# TEC_CTRL.net
KiCad netlist of a schematic drawn in Altium Designer
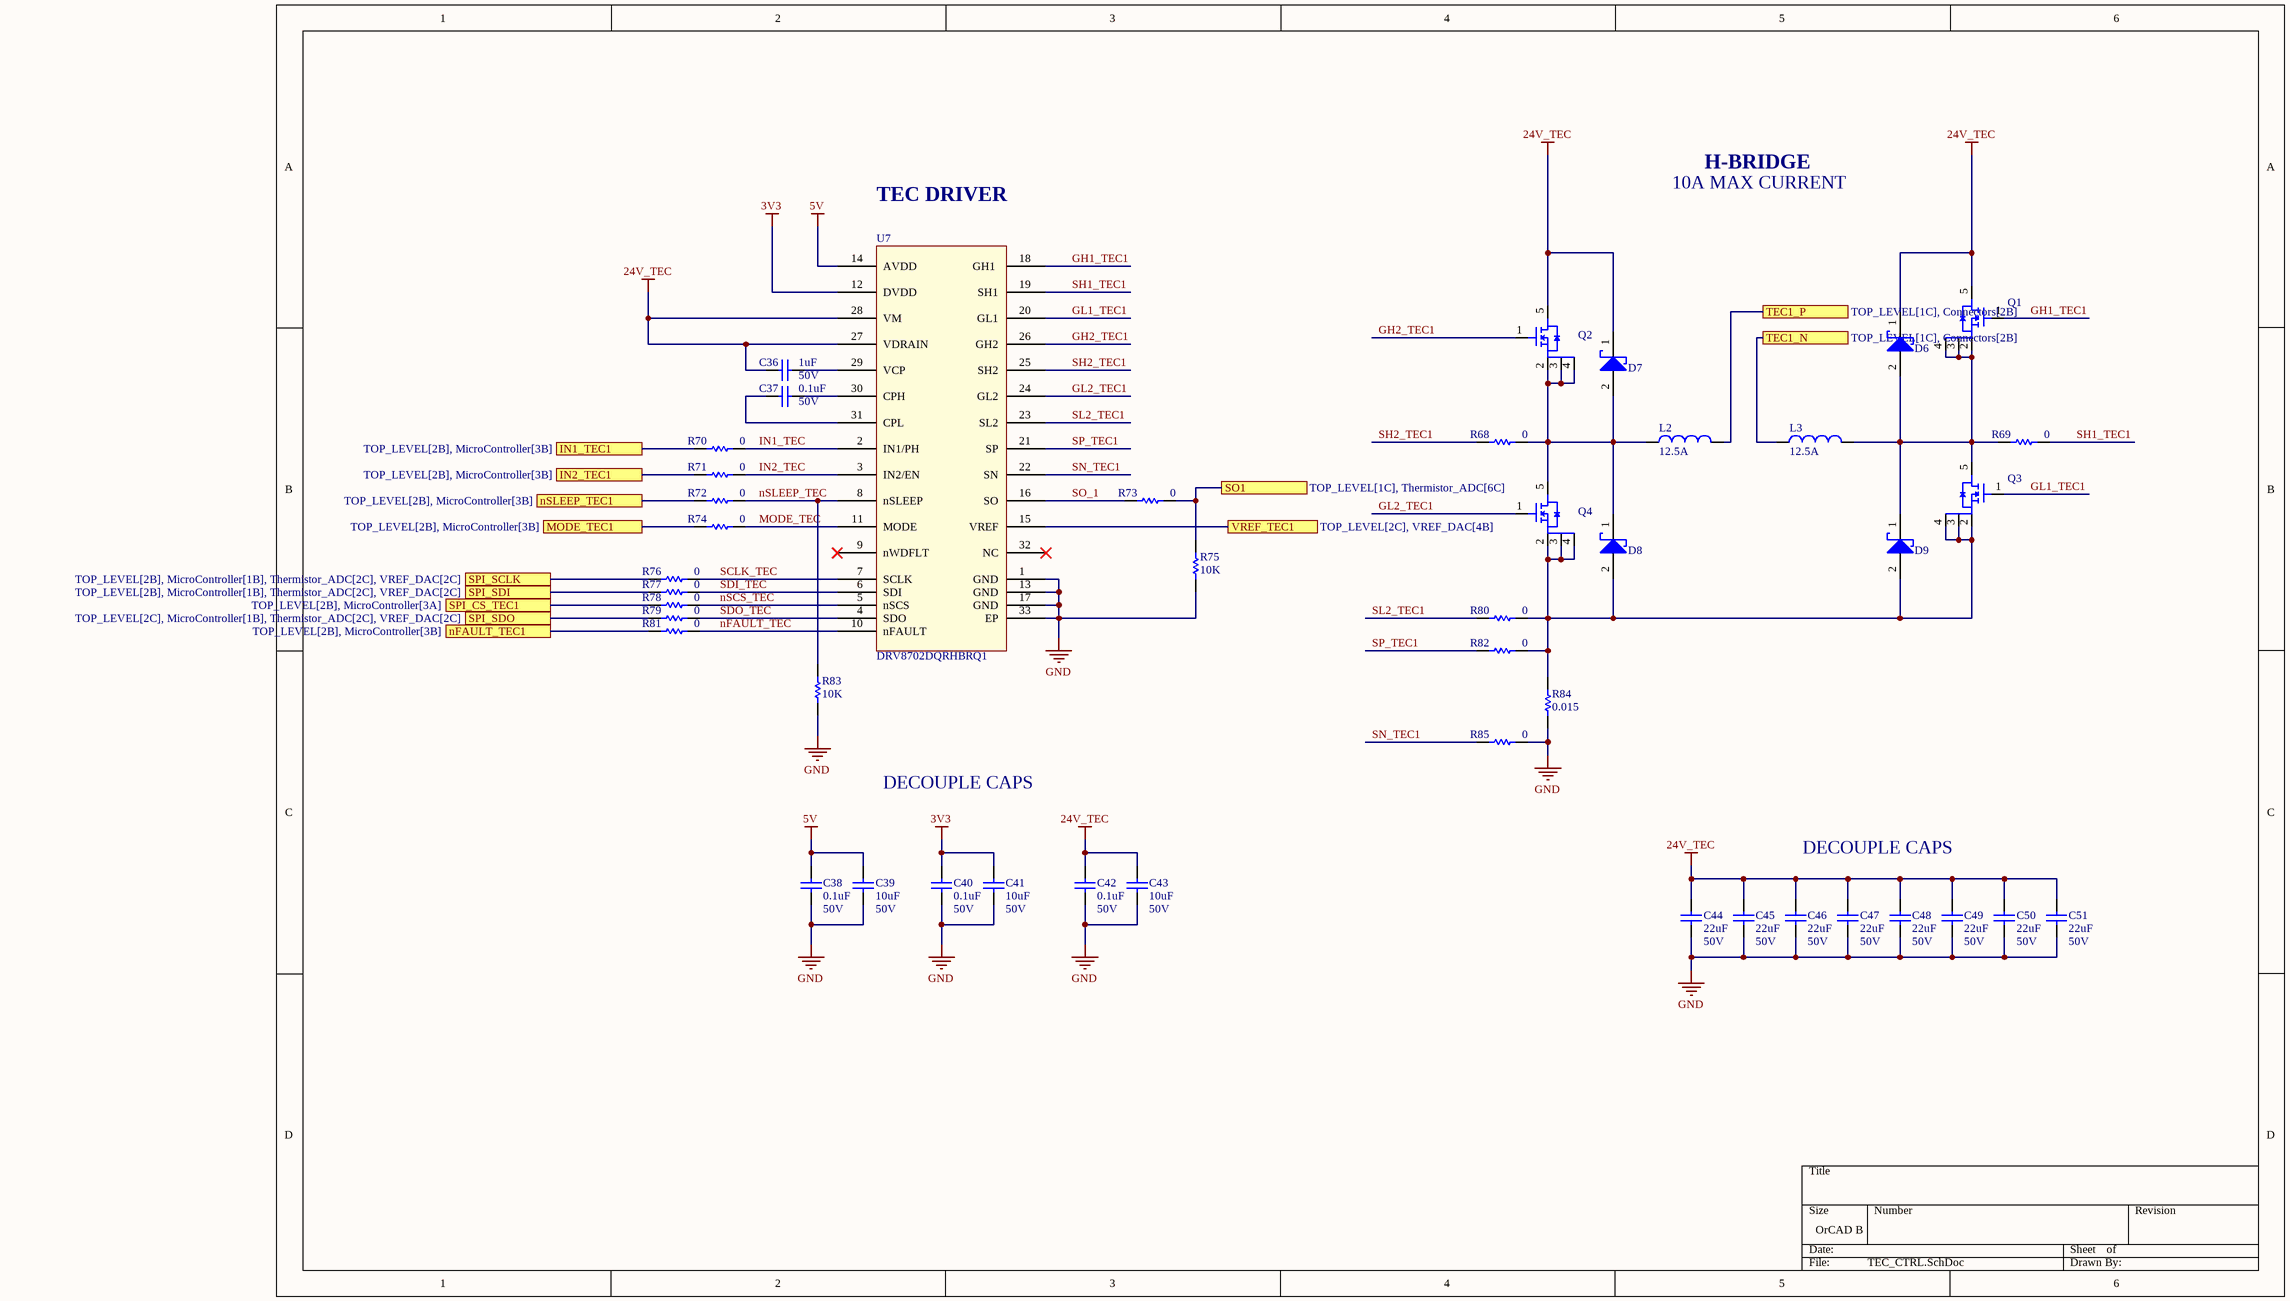
[diagram p0: TEC_CTRL.SchDoc]

(export (version "E")
  (design (tool "Eeschema 10.0.6"))
  (components
    (comp (ref "C36")
      (value "1uF")
      (footprint "DEFAULT_CAPACITOR_0805")
      (description "CAP CER 1UF 50V X7R 0805")
      (fields (field (name "RATING") "50V") (field (name "Comment") "CL21B105KBFNNNE"))
      (libsource (lib "Avery Altium Llibrary") (part "CL21B105KBFNNNE"))
    )
    (comp (ref "C37")
      (value "0.1uF")
      (footprint "DEFAULT_CAPACITOR_0805")
      (description "CAP CER 0.1UF 50V X7R 0805")
      (fields
        (field (name "MANUFACTURER") "Cal-Chip Electronics, Inc.")
        (field (name "RATING") "50V")
        (field (name "Comment") "KGM21NR71H104KT")
      )
      (libsource (lib "Avery Altium Llibrary") (part "KGM21NR71H104KT"))
    )
    (comp (ref "C38")
      (value "0.1uF")
      (footprint "DEFAULT_CAPACITOR_0805")
      (description "CAP CER 0.1UF 50V X7R 0805")
      (fields
        (field (name "MANUFACTURER") "Cal-Chip Electronics, Inc.")
        (field (name "RATING") "50V")
        (field (name "Comment") "KGM21NR71H104KT")
      )
      (libsource (lib "Avery Altium Llibrary") (part "KGM21NR71H104KT"))
    )
    (comp (ref "C39")
      (value "10uF")
      (footprint "DEFAULT_CAPACITOR_0805")
      (description "CAP CER 10UF 50V X5R 0805")
      (fields (field (name "RATING") "50V") (field (name "Comment") "GRM21BR61H106KE43L"))
      (libsource (lib "Avery Altium Llibrary") (part "GRM21BR61H106KE43L"))
    )
    (comp (ref "C40")
      (value "0.1uF")
      (footprint "DEFAULT_CAPACITOR_0805")
      (description "CAP CER 0.1UF 50V X7R 0805")
      (fields
        (field (name "MANUFACTURER") "Cal-Chip Electronics, Inc.")
        (field (name "RATING") "50V")
        (field (name "Comment") "KGM21NR71H104KT")
      )
      (libsource (lib "Avery Altium Llibrary") (part "KGM21NR71H104KT"))
    )
    (comp (ref "C41")
      (value "10uF")
      (footprint "DEFAULT_CAPACITOR_0805")
      (description "CAP CER 10UF 50V X5R 0805")
      (fields (field (name "RATING") "50V") (field (name "Comment") "GRM21BR61H106KE43L"))
      (libsource (lib "Avery Altium Llibrary") (part "GRM21BR61H106KE43L"))
    )
    (comp (ref "C42")
      (value "0.1uF")
      (footprint "DEFAULT_CAPACITOR_0805")
      (description "CAP CER 0.1UF 50V X7R 0805")
      (fields
        (field (name "MANUFACTURER") "Cal-Chip Electronics, Inc.")
        (field (name "RATING") "50V")
        (field (name "Comment") "KGM21NR71H104KT")
      )
      (libsource (lib "Avery Altium Llibrary") (part "KGM21NR71H104KT"))
    )
    (comp (ref "C43")
      (value "10uF")
      (footprint "DEFAULT_CAPACITOR_0805")
      (description "CAP CER 10UF 50V X5R 0805")
      (fields (field (name "RATING") "50V") (field (name "Comment") "GRM21BR61H106KE43L"))
      (libsource (lib "Avery Altium Llibrary") (part "GRM21BR61H106KE43L"))
    )
    (comp (ref "C44")
      (value "22uF")
      (footprint "DEFAULT_CAPACITOR_2220")
      (description "CAP CER 22UF 50V X7R 2220")
      (fields (field (name "RATING") "50V") (field (name "Comment") "C5750X7R1H226M250KB"))
      (libsource (lib "Avery Altium Llibrary") (part "C5750X7R1H226M250KB"))
    )
    (comp (ref "C45")
      (value "22uF")
      (footprint "DEFAULT_CAPACITOR_2220")
      (description "CAP CER 22UF 50V X7R 2220")
      (fields (field (name "RATING") "50V") (field (name "Comment") "C5750X7R1H226M250KB"))
      (libsource (lib "Avery Altium Llibrary") (part "C5750X7R1H226M250KB"))
    )
    (comp (ref "C46")
      (value "22uF")
      (footprint "DEFAULT_CAPACITOR_2220")
      (description "CAP CER 22UF 50V X7R 2220")
      (fields (field (name "RATING") "50V") (field (name "Comment") "C5750X7R1H226M250KB"))
      (libsource (lib "Avery Altium Llibrary") (part "C5750X7R1H226M250KB"))
    )
    (comp (ref "C47")
      (value "22uF")
      (footprint "DEFAULT_CAPACITOR_2220")
      (description "CAP CER 22UF 50V X7R 2220")
      (fields (field (name "RATING") "50V") (field (name "Comment") "C5750X7R1H226M250KB"))
      (libsource (lib "Avery Altium Llibrary") (part "C5750X7R1H226M250KB"))
    )
    (comp (ref "C48")
      (value "22uF")
      (footprint "DEFAULT_CAPACITOR_2220")
      (description "CAP CER 22UF 50V X7R 2220")
      (fields (field (name "RATING") "50V") (field (name "Comment") "C5750X7R1H226M250KB"))
      (libsource (lib "Avery Altium Llibrary") (part "C5750X7R1H226M250KB"))
    )
    (comp (ref "C49")
      (value "22uF")
      (footprint "DEFAULT_CAPACITOR_2220")
      (description "CAP CER 22UF 50V X7R 2220")
      (fields (field (name "RATING") "50V") (field (name "Comment") "C5750X7R1H226M250KB"))
      (libsource (lib "Avery Altium Llibrary") (part "C5750X7R1H226M250KB"))
    )
    (comp (ref "C50")
      (value "22uF")
      (footprint "DEFAULT_CAPACITOR_2220")
      (description "CAP CER 22UF 50V X7R 2220")
      (fields (field (name "RATING") "50V") (field (name "Comment") "C5750X7R1H226M250KB"))
      (libsource (lib "Avery Altium Llibrary") (part "C5750X7R1H226M250KB"))
    )
    (comp (ref "C51")
      (value "22uF")
      (footprint "DEFAULT_CAPACITOR_2220")
      (description "CAP CER 22UF 50V X7R 2220")
      (fields (field (name "RATING") "50V") (field (name "Comment") "C5750X7R1H226M250KB"))
      (libsource (lib "Avery Altium Llibrary") (part "C5750X7R1H226M250KB"))
    )
    (comp (ref "D6")
      (value "B2100Q-13-F")
      (footprint "B2100Q-13-F-SMB")
      (description "DIODE SCHOTTKY 100V 2A SMB")
      (fields (field (name "MANUFACTURER") "Diodes Incorporated"))
      (libsource (lib "Avery Altium Llibrary") (part "B2100Q-13-F"))
    )
    (comp (ref "D7")
      (value "B2100Q-13-F")
      (footprint "B2100Q-13-F-SMB")
      (description "DIODE SCHOTTKY 100V 2A SMB")
      (fields (field (name "MANUFACTURER") "Diodes Incorporated"))
      (libsource (lib "Avery Altium Llibrary") (part "B2100Q-13-F"))
    )
    (comp (ref "D8")
      (value "B2100Q-13-F")
      (footprint "B2100Q-13-F-SMB")
      (description "DIODE SCHOTTKY 100V 2A SMB")
      (fields (field (name "MANUFACTURER") "Diodes Incorporated"))
      (libsource (lib "Avery Altium Llibrary") (part "B2100Q-13-F"))
    )
    (comp (ref "D9")
      (value "B2100Q-13-F")
      (footprint "B2100Q-13-F-SMB")
      (description "DIODE SCHOTTKY 100V 2A SMB")
      (fields (field (name "MANUFACTURER") "Diodes Incorporated"))
      (libsource (lib "Avery Altium Llibrary") (part "B2100Q-13-F"))
    )
    (comp (ref "L2")
      (value "SRP1770TA-150M")
      (footprint "BOURNS-SRP1770TA")
      (description "FIXED IND 15UH 12.5A 20.5MOHM SM")
      (fields (field (name "MANUFACTURER") "Bourns Inc.") (field (name "RATING") "12.5A"))
      (libsource (lib "Avery Schem Library") (part "SRP1770TA-150M"))
    )
    (comp (ref "L3")
      (value "SRP1770TA-150M")
      (footprint "BOURNS-SRP1770TA")
      (description "FIXED IND 15UH 12.5A 20.5MOHM SM")
      (fields (field (name "MANUFACTURER") "Bourns Inc.") (field (name "RATING") "12.5A"))
      (libsource (lib "Avery Schem Library") (part "SRP1770TA-150M"))
    )
    (comp (ref "Q1")
      (value "BUK7S2R0-40HJ")
      (footprint "BUK7S2R0-40HJ-SOT1235")
      (description "N-Channel 40 V 190A (Tc) 183W (Tc) Surface Mount LFPAK88 (SOT1235)")
      (fields (field (name "MANUFACTURER") "Nexperia USA Inc."))
      (libsource (lib "Avery Altium Llibrary") (part "BUK7S2R0-40HJ"))
    )
    (comp (ref "Q2")
      (value "BUK7S2R0-40HJ")
      (footprint "BUK7S2R0-40HJ-SOT1235")
      (description "N-Channel 40 V 190A (Tc) 183W (Tc) Surface Mount LFPAK88 (SOT1235)")
      (fields (field (name "MANUFACTURER") "Nexperia USA Inc."))
      (libsource (lib "Avery Altium Llibrary") (part "BUK7S2R0-40HJ"))
    )
    (comp (ref "Q3")
      (value "BUK7S2R0-40HJ")
      (footprint "BUK7S2R0-40HJ-SOT1235")
      (description "N-Channel 40 V 190A (Tc) 183W (Tc) Surface Mount LFPAK88 (SOT1235)")
      (fields (field (name "MANUFACTURER") "Nexperia USA Inc."))
      (libsource (lib "Avery Altium Llibrary") (part "BUK7S2R0-40HJ"))
    )
    (comp (ref "Q4")
      (value "BUK7S2R0-40HJ")
      (footprint "BUK7S2R0-40HJ-SOT1235")
      (description "N-Channel 40 V 190A (Tc) 183W (Tc) Surface Mount LFPAK88 (SOT1235)")
      (fields (field (name "MANUFACTURER") "Nexperia USA Inc."))
      (libsource (lib "Avery Altium Llibrary") (part "BUK7S2R0-40HJ"))
    )
    (comp (ref "R68")
      (value "0")
      (footprint "DEFAULT_RESISTOR_0805")
      (description "RES 0 OHM JUMPER 1/8W 0805")
      (fields (field (name "POWER") "1/8W") (field (name "Comment") "RC0805JR-070RL"))
      (libsource (lib "Avery Altium Llibrary") (part "RC0805JR-070RL"))
    )
    (comp (ref "R69")
      (value "0")
      (footprint "DEFAULT_RESISTOR_0805")
      (description "RES 0 OHM JUMPER 1/8W 0805")
      (fields (field (name "POWER") "1/8W") (field (name "Comment") "RC0805JR-070RL"))
      (libsource (lib "Avery Altium Llibrary") (part "RC0805JR-070RL"))
    )
    (comp (ref "R70")
      (value "0")
      (footprint "DEFAULT_RESISTOR_0805")
      (description "RES 0 OHM JUMPER 1/8W 0805")
      (fields (field (name "POWER") "1/8W") (field (name "Comment") "RC0805JR-070RL"))
      (libsource (lib "Avery Altium Llibrary") (part "RC0805JR-070RL"))
    )
    (comp (ref "R71")
      (value "0")
      (footprint "DEFAULT_RESISTOR_0805")
      (description "RES 0 OHM JUMPER 1/8W 0805")
      (fields (field (name "POWER") "1/8W") (field (name "Comment") "RC0805JR-070RL"))
      (libsource (lib "Avery Altium Llibrary") (part "RC0805JR-070RL"))
    )
    (comp (ref "R72")
      (value "0")
      (footprint "DEFAULT_RESISTOR_0805")
      (description "RES 0 OHM JUMPER 1/8W 0805")
      (fields (field (name "POWER") "1/8W") (field (name "Comment") "RC0805JR-070RL"))
      (libsource (lib "Avery Altium Llibrary") (part "RC0805JR-070RL"))
    )
    (comp (ref "R73")
      (value "0")
      (footprint "DEFAULT_RESISTOR_0805")
      (description "RES 0 OHM JUMPER 1/8W 0805")
      (fields (field (name "POWER") "1/8W") (field (name "Comment") "RC0805JR-070RL"))
      (libsource (lib "Avery Altium Llibrary") (part "RC0805JR-070RL"))
    )
    (comp (ref "R74")
      (value "0")
      (footprint "DEFAULT_RESISTOR_0805")
      (description "RES 0 OHM JUMPER 1/8W 0805")
      (fields (field (name "POWER") "1/8W") (field (name "Comment") "RC0805JR-070RL"))
      (libsource (lib "Avery Altium Llibrary") (part "RC0805JR-070RL"))
    )
    (comp (ref "R75")
      (value "10K")
      (footprint "DEFAULT_RESISTOR_0805")
      (description "RES SMD 10K OHM 1% 1/4W 0805")
      (fields (field (name "POWER") "1/4W") (field (name "TOLERANCE") "1%"))
      (libsource (lib "Avery Altium Llibrary") (part "CRCW080510K0FKEA"))
    )
    (comp (ref "R76")
      (value "0")
      (footprint "DEFAULT_RESISTOR_0805")
      (description "RES 0 OHM JUMPER 1/8W 0805")
      (fields (field (name "POWER") "1/8W") (field (name "Comment") "RC0805JR-070RL"))
      (libsource (lib "Avery Altium Llibrary") (part "RC0805JR-070RL"))
    )
    (comp (ref "R77")
      (value "0")
      (footprint "DEFAULT_RESISTOR_0805")
      (description "RES 0 OHM JUMPER 1/8W 0805")
      (fields (field (name "POWER") "1/8W") (field (name "Comment") "RC0805JR-070RL"))
      (libsource (lib "Avery Altium Llibrary") (part "RC0805JR-070RL"))
    )
    (comp (ref "R78")
      (value "0")
      (footprint "DEFAULT_RESISTOR_0805")
      (description "RES 0 OHM JUMPER 1/8W 0805")
      (fields (field (name "POWER") "1/8W") (field (name "Comment") "RC0805JR-070RL"))
      (libsource (lib "Avery Altium Llibrary") (part "RC0805JR-070RL"))
    )
    (comp (ref "R79")
      (value "0")
      (footprint "DEFAULT_RESISTOR_0805")
      (description "RES 0 OHM JUMPER 1/8W 0805")
      (fields (field (name "POWER") "1/8W") (field (name "Comment") "RC0805JR-070RL"))
      (libsource (lib "Avery Altium Llibrary") (part "RC0805JR-070RL"))
    )
    (comp (ref "R80")
      (value "0")
      (footprint "DEFAULT_RESISTOR_0805")
      (description "RES 0 OHM JUMPER 1/8W 0805")
      (fields (field (name "POWER") "1/8W") (field (name "Comment") "RC0805JR-070RL"))
      (libsource (lib "Avery Altium Llibrary") (part "RC0805JR-070RL"))
    )
    (comp (ref "R81")
      (value "0")
      (footprint "DEFAULT_RESISTOR_0805")
      (description "RES 0 OHM JUMPER 1/8W 0805")
      (fields (field (name "POWER") "1/8W") (field (name "Comment") "RC0805JR-070RL"))
      (libsource (lib "Avery Altium Llibrary") (part "RC0805JR-070RL"))
    )
    (comp (ref "R82")
      (value "0")
      (footprint "DEFAULT_RESISTOR_0805")
      (description "RES 0 OHM JUMPER 1/8W 0805")
      (fields (field (name "POWER") "1/8W") (field (name "Comment") "RC0805JR-070RL"))
      (libsource (lib "Avery Altium Llibrary") (part "RC0805JR-070RL"))
    )
    (comp (ref "R83")
      (value "10K")
      (footprint "DEFAULT_RESISTOR_0805")
      (description "RES SMD 10K OHM 1% 1/4W 0805")
      (fields (field (name "POWER") "1/4W") (field (name "TOLERANCE") "1%"))
      (libsource (lib "Avery Altium Llibrary") (part "CRCW080510K0FKEA"))
    )
    (comp (ref "R84")
      (value "0.015")
      (footprint "DEFAULT_RESISTOR_2512")
      (description "RES 0.015 OHM 1% 3W 2512")
      (fields (field (name "POWER") "3W") (field (name "TOLERANCE") "1%"))
      (libsource (lib "Avery Altium Llibrary") (part "CRA2512-FZ-R015ELF"))
    )
    (comp (ref "R85")
      (value "0")
      (footprint "DEFAULT_RESISTOR_0805")
      (description "RES 0 OHM JUMPER 1/8W 0805")
      (fields (field (name "POWER") "1/8W") (field (name "Comment") "RC0805JR-070RL"))
      (libsource (lib "Avery Altium Llibrary") (part "RC0805JR-070RL"))
    )
    (comp (ref "U7")
      (value "DRV8702DQRHBRQ1")
      (footprint "DRV8702DQRHBRQ1-32VQFN")
      (description "IC MOTOR DRIVER 5.5V-45V 32VQFN")
      (fields
        (field (name "MANUFACTURER") "Texas Instruments")
        (field (name "MANUFACTURER P/N") "DRV8702DQRHBRQ1")
      )
      (libsource (lib "Avery Altium Llibrary") (part "DRV8702DQRHBRQ1"))
    )
  )
  (nets
    (net (code "1") (name "/GH1_TEC1") (class "Default")
      (node (ref "Q1") (pin "1") (pinfunction "G_1") (pintype "passive"))
      (node (ref "U7") (pin "18") (pinfunction "GH1_18") (pintype "passive"))
    )
    (net (code "2") (name "/GH2_TEC1") (class "Default")
      (node (ref "Q2") (pin "1") (pinfunction "G_1") (pintype "passive"))
      (node (ref "U7") (pin "26") (pinfunction "GH2_26") (pintype "passive"))
    )
    (net (code "3") (name "/GL1_TEC1") (class "Default")
      (node (ref "Q3") (pin "1") (pinfunction "G_1") (pintype "passive"))
      (node (ref "U7") (pin "20") (pinfunction "GL1_20") (pintype "passive"))
    )
    (net (code "4") (name "/GL2_TEC1") (class "Default")
      (node (ref "Q4") (pin "1") (pinfunction "G_1") (pintype "passive"))
      (node (ref "U7") (pin "24") (pinfunction "GL2_24") (pintype "passive"))
    )
    (net (code "5") (name "/IN1_TEC") (class "Default")
      (node (ref "R70") (pin "1") (pinfunction "1_1") (pintype "passive"))
      (node (ref "U7") (pin "2") (pinfunction "IN1/PH_2") (pintype "passive"))
    )
    (net (code "6") (name "/IN1_TEC1") (class "Default")
      (node (ref "R70") (pin "2") (pinfunction "2_2") (pintype "passive"))
    )
    (net (code "7") (name "/IN2_TEC") (class "Default")
      (node (ref "R71") (pin "1") (pinfunction "1_1") (pintype "passive"))
      (node (ref "U7") (pin "3") (pinfunction "IN2/EN_3") (pintype "passive"))
    )
    (net (code "8") (name "/IN2_TEC1") (class "Default")
      (node (ref "R71") (pin "2") (pinfunction "2_2") (pintype "passive"))
    )
    (net (code "9") (name "/MODE_TEC") (class "Default")
      (node (ref "R74") (pin "1") (pinfunction "1_1") (pintype "passive"))
      (node (ref "U7") (pin "11") (pinfunction "MODE_11") (pintype "passive"))
    )
    (net (code "10") (name "/MODE_TEC1") (class "Default")
      (node (ref "R74") (pin "2") (pinfunction "2_2") (pintype "passive"))
    )
    (net (code "11") (name "/SCLK_TEC") (class "Default")
      (node (ref "R76") (pin "1") (pinfunction "1_1") (pintype "passive"))
      (node (ref "U7") (pin "7") (pinfunction "SCLK_7") (pintype "passive"))
    )
    (net (code "12") (name "/SDI_TEC") (class "Default")
      (node (ref "R77") (pin "1") (pinfunction "1_1") (pintype "passive"))
      (node (ref "U7") (pin "6") (pinfunction "SDI_6") (pintype "passive"))
    )
    (net (code "13") (name "/SDO_TEC") (class "Default")
      (node (ref "R79") (pin "1") (pinfunction "1_1") (pintype "passive"))
      (node (ref "U7") (pin "4") (pinfunction "SDO_4") (pintype "passive"))
    )
    (net (code "14") (name "/SH1_TEC1") (class "Default")
      (node (ref "R69") (pin "1") (pinfunction "1_1") (pintype "passive"))
      (node (ref "U7") (pin "19") (pinfunction "SH1_19") (pintype "passive"))
    )
    (net (code "15") (name "/SH2_TEC1") (class "Default")
      (node (ref "R68") (pin "2") (pinfunction "2_2") (pintype "passive"))
      (node (ref "U7") (pin "25") (pinfunction "SH2_25") (pintype "passive"))
    )
    (net (code "16") (name "/SL2_TEC1") (class "Default")
      (node (ref "R80") (pin "2") (pinfunction "2_2") (pintype "passive"))
      (node (ref "U7") (pin "23") (pinfunction "SL2_23") (pintype "passive"))
    )
    (net (code "17") (name "/SN_TEC1") (class "Default")
      (node (ref "R85") (pin "2") (pinfunction "2_2") (pintype "passive"))
      (node (ref "U7") (pin "22") (pinfunction "SN_22") (pintype "passive"))
    )
    (net (code "18") (name "/SO1") (class "Default")
      (node (ref "R73") (pin "1") (pinfunction "1_1") (pintype "passive"))
      (node (ref "R75") (pin "1") (pinfunction "1_1") (pintype "passive"))
    )
    (net (code "19") (name "/SO_1") (class "Default")
      (node (ref "R73") (pin "2") (pinfunction "2_2") (pintype "passive"))
      (node (ref "U7") (pin "16") (pinfunction "SO_16") (pintype "passive"))
    )
    (net (code "20") (name "/SPI_CS_TEC1") (class "Default")
      (node (ref "R78") (pin "2") (pinfunction "2_2") (pintype "passive"))
    )
    (net (code "21") (name "/SPI_SCLK") (class "Default")
      (node (ref "R76") (pin "2") (pinfunction "2_2") (pintype "passive"))
    )
    (net (code "22") (name "/SPI_SDI") (class "Default")
      (node (ref "R77") (pin "2") (pinfunction "2_2") (pintype "passive"))
    )
    (net (code "23") (name "/SPI_SDO") (class "Default")
      (node (ref "R79") (pin "2") (pinfunction "2_2") (pintype "passive"))
    )
    (net (code "24") (name "/SP_TEC1") (class "Default")
      (node (ref "R82") (pin "2") (pinfunction "2_2") (pintype "passive"))
      (node (ref "U7") (pin "21") (pinfunction "SP_21") (pintype "passive"))
    )
    (net (code "25") (name "/TEC1_N") (class "Default")
      (node (ref "L3") (pin "1") (pinfunction "1_1") (pintype "passive"))
    )
    (net (code "26") (name "/TEC1_P") (class "Default")
      (node (ref "L2") (pin "2") (pinfunction "2_2") (pintype "passive"))
    )
    (net (code "27") (name "/VREF_TEC1") (class "Default")
      (node (ref "U7") (pin "15") (pinfunction "VREF_15") (pintype "passive"))
    )
    (net (code "28") (name "/nFAULT_TEC") (class "Default")
      (node (ref "R81") (pin "1") (pinfunction "1_1") (pintype "passive"))
      (node (ref "U7") (pin "10") (pinfunction "nFAULT_10") (pintype "passive"))
    )
    (net (code "29") (name "/nFAULT_TEC1") (class "Default")
      (node (ref "R81") (pin "2") (pinfunction "2_2") (pintype "passive"))
    )
    (net (code "30") (name "/nSCS_TEC") (class "Default")
      (node (ref "R78") (pin "1") (pinfunction "1_1") (pintype "passive"))
      (node (ref "U7") (pin "5") (pinfunction "nSCS_5") (pintype "passive"))
    )
    (net (code "31") (name "/nSLEEP_TEC") (class "Default")
      (node (ref "R72") (pin "1") (pinfunction "1_1") (pintype "passive"))
      (node (ref "R83") (pin "1") (pinfunction "1_1") (pintype "passive"))
      (node (ref "U7") (pin "8") (pinfunction "nSLEEP_8") (pintype "passive"))
    )
    (net (code "32") (name "/nSLEEP_TEC1") (class "Default")
      (node (ref "R72") (pin "2") (pinfunction "2_2") (pintype "passive"))
    )
    (net (code "33") (name "3V3") (class "Default")
      (node (ref "C40") (pin "2") (pinfunction "2_2") (pintype "passive"))
      (node (ref "C41") (pin "2") (pinfunction "2_2") (pintype "passive"))
      (node (ref "U7") (pin "12") (pinfunction "DVDD_12") (pintype "passive"))
    )
    (net (code "34") (name "5V") (class "Default")
      (node (ref "C38") (pin "2") (pinfunction "2_2") (pintype "passive"))
      (node (ref "C39") (pin "2") (pinfunction "2_2") (pintype "passive"))
      (node (ref "U7") (pin "14") (pinfunction "AVDD_14") (pintype "passive"))
    )
    (net (code "35") (name "24V_TEC") (class "Default")
      (node (ref "C36") (pin "2") (pinfunction "2_2") (pintype "passive"))
      (node (ref "C42") (pin "2") (pinfunction "2_2") (pintype "passive"))
      (node (ref "C43") (pin "2") (pinfunction "2_2") (pintype "passive"))
      (node (ref "C44") (pin "2") (pinfunction "2_2") (pintype "passive"))
      (node (ref "C45") (pin "2") (pinfunction "2_2") (pintype "passive"))
      (node (ref "C46") (pin "2") (pinfunction "2_2") (pintype "passive"))
      (node (ref "C47") (pin "2") (pinfunction "2_2") (pintype "passive"))
      (node (ref "C48") (pin "2") (pinfunction "2_2") (pintype "passive"))
      (node (ref "C49") (pin "2") (pinfunction "2_2") (pintype "passive"))
      (node (ref "C50") (pin "2") (pinfunction "2_2") (pintype "passive"))
      (node (ref "C51") (pin "2") (pinfunction "2_2") (pintype "passive"))
      (node (ref "D6") (pin "1") (pinfunction "K_1") (pintype "passive"))
      (node (ref "D7") (pin "1") (pinfunction "K_1") (pintype "passive"))
      (node (ref "Q1") (pin "5") (pinfunction "D_5") (pintype "passive"))
      (node (ref "Q2") (pin "5") (pinfunction "D_5") (pintype "passive"))
      (node (ref "U7") (pin "27") (pinfunction "VDRAIN_27") (pintype "passive"))
      (node (ref "U7") (pin "28") (pinfunction "VM_28") (pintype "passive"))
    )
    (net (code "36") (name "GND") (class "Default")
      (node (ref "C38") (pin "1") (pinfunction "1_1") (pintype "passive"))
      (node (ref "C39") (pin "1") (pinfunction "1_1") (pintype "passive"))
      (node (ref "C40") (pin "1") (pinfunction "1_1") (pintype "passive"))
      (node (ref "C41") (pin "1") (pinfunction "1_1") (pintype "passive"))
      (node (ref "C42") (pin "1") (pinfunction "1_1") (pintype "passive"))
      (node (ref "C43") (pin "1") (pinfunction "1_1") (pintype "passive"))
      (node (ref "C44") (pin "1") (pinfunction "1_1") (pintype "passive"))
      (node (ref "C45") (pin "1") (pinfunction "1_1") (pintype "passive"))
      (node (ref "C46") (pin "1") (pinfunction "1_1") (pintype "passive"))
      (node (ref "C47") (pin "1") (pinfunction "1_1") (pintype "passive"))
      (node (ref "C48") (pin "1") (pinfunction "1_1") (pintype "passive"))
      (node (ref "C49") (pin "1") (pinfunction "1_1") (pintype "passive"))
      (node (ref "C50") (pin "1") (pinfunction "1_1") (pintype "passive"))
      (node (ref "C51") (pin "1") (pinfunction "1_1") (pintype "passive"))
      (node (ref "R75") (pin "2") (pinfunction "2_2") (pintype "passive"))
      (node (ref "R83") (pin "2") (pinfunction "2_2") (pintype "passive"))
      (node (ref "R84") (pin "2") (pinfunction "2_2") (pintype "passive"))
      (node (ref "R85") (pin "1") (pinfunction "1_1") (pintype "passive"))
      (node (ref "U7") (pin "1") (pinfunction "GND_1") (pintype "passive"))
      (node (ref "U7") (pin "13") (pinfunction "GND_13") (pintype "passive"))
      (node (ref "U7") (pin "17") (pinfunction "GND_17") (pintype "passive"))
      (node (ref "U7") (pin "33") (pinfunction "EP_33") (pintype "passive"))
    )
    (net (code "37") (name "Net-(D6-A)") (class "Default")
      (node (ref "D6") (pin "2") (pinfunction "A_2") (pintype "passive"))
      (node (ref "D9") (pin "1") (pinfunction "K_1") (pintype "passive"))
      (node (ref "L3") (pin "2") (pinfunction "2_2") (pintype "passive"))
      (node (ref "Q1") (pin "2") (pinfunction "D_2") (pintype "passive"))
      (node (ref "Q1") (pin "3") (pinfunction "S_3") (pintype "passive"))
      (node (ref "Q1") (pin "4") (pinfunction "D_4") (pintype "passive"))
      (node (ref "Q3") (pin "5") (pinfunction "D_5") (pintype "passive"))
      (node (ref "R69") (pin "2") (pinfunction "2_2") (pintype "passive"))
    )
    (net (code "38") (name "Net-(D7-A)") (class "Default")
      (node (ref "D7") (pin "2") (pinfunction "A_2") (pintype "passive"))
      (node (ref "D8") (pin "1") (pinfunction "K_1") (pintype "passive"))
      (node (ref "L2") (pin "1") (pinfunction "1_1") (pintype "passive"))
      (node (ref "Q2") (pin "2") (pinfunction "D_2") (pintype "passive"))
      (node (ref "Q2") (pin "3") (pinfunction "S_3") (pintype "passive"))
      (node (ref "Q2") (pin "4") (pinfunction "D_4") (pintype "passive"))
      (node (ref "Q4") (pin "5") (pinfunction "D_5") (pintype "passive"))
      (node (ref "R68") (pin "1") (pinfunction "1_1") (pintype "passive"))
    )
    (net (code "39") (name "Net-(D8-A)") (class "Default")
      (node (ref "D8") (pin "2") (pinfunction "A_2") (pintype "passive"))
      (node (ref "D9") (pin "2") (pinfunction "A_2") (pintype "passive"))
      (node (ref "Q3") (pin "2") (pinfunction "D_2") (pintype "passive"))
      (node (ref "Q3") (pin "3") (pinfunction "S_3") (pintype "passive"))
      (node (ref "Q3") (pin "4") (pinfunction "D_4") (pintype "passive"))
      (node (ref "Q4") (pin "2") (pinfunction "D_2") (pintype "passive"))
      (node (ref "Q4") (pin "3") (pinfunction "S_3") (pintype "passive"))
      (node (ref "Q4") (pin "4") (pinfunction "D_4") (pintype "passive"))
      (node (ref "R80") (pin "1") (pinfunction "1_1") (pintype "passive"))
      (node (ref "R82") (pin "1") (pinfunction "1_1") (pintype "passive"))
      (node (ref "R84") (pin "1") (pinfunction "1_1") (pintype "passive"))
    )
    (net (code "40") (name "Net-(U7-CPH)") (class "Default")
      (node (ref "C37") (pin "1") (pinfunction "1_1") (pintype "passive"))
      (node (ref "U7") (pin "30") (pinfunction "CPH_30") (pintype "passive"))
    )
    (net (code "41") (name "Net-(U7-CPL)") (class "Default")
      (node (ref "C37") (pin "2") (pinfunction "2_2") (pintype "passive"))
      (node (ref "U7") (pin "31") (pinfunction "CPL_31") (pintype "passive"))
    )
    (net (code "42") (name "Net-(U7-VCP)") (class "Default")
      (node (ref "C36") (pin "1") (pinfunction "1_1") (pintype "passive"))
      (node (ref "U7") (pin "29") (pinfunction "VCP_29") (pintype "passive"))
    )
    (net (code "43") (name "unconnected-(U7-NC-Pad32)") (class "Default")
      (node (ref "U7") (pin "32") (pinfunction "NC_32") (pintype "passive+no_connect"))
    )
    (net (code "44") (name "unconnected-(U7-nWDFLT-Pad9)") (class "Default")
      (node (ref "U7") (pin "9") (pinfunction "nWDFLT_9") (pintype "passive+no_connect"))
    )
  )
)
